# PCB.net
KiCad netlist of a schematic drawn in EAGLE
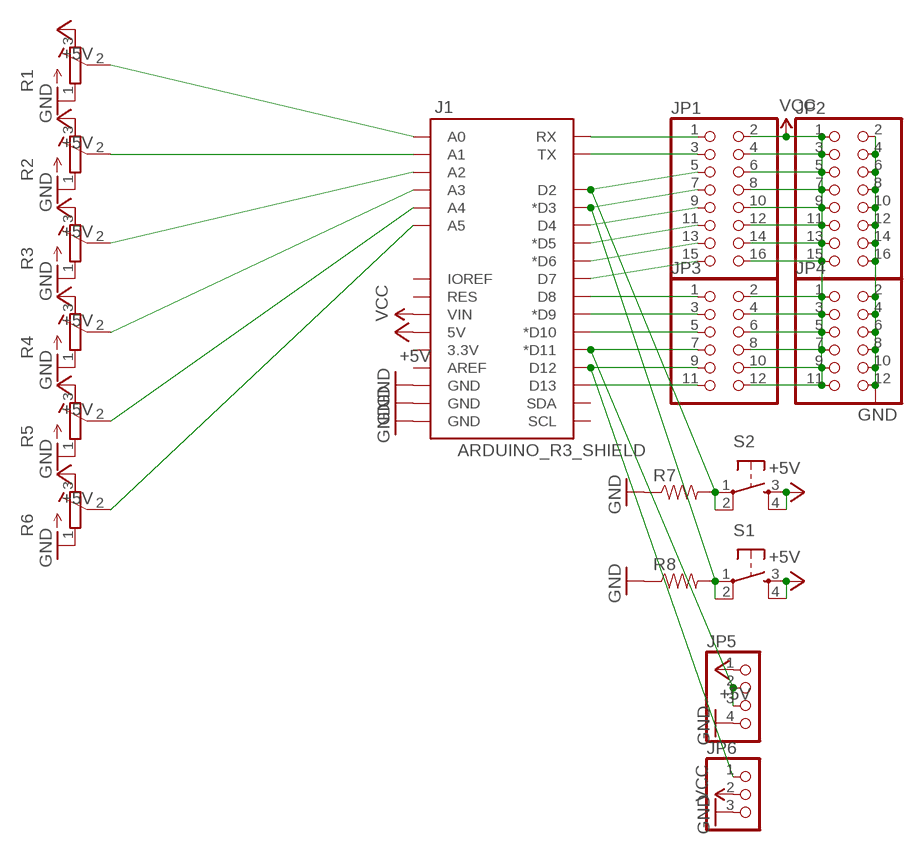
[diagram p0: schematic, sheet 1]

(export (version "E")
  (design (tool "Eeschema 10.0.6"))
  (components
    (comp (ref "J1")
      (value "ARDUINO_R3_SHIELD")
      (footprint "eagle-import:UNO_R3_SHIELD")
      (libsource (lib "eagle-import") (part "ARDUINO_R3_SHIELD"))
    )
    (comp (ref "JP1")
      (value "PINHD-2X8")
      (footprint "eagle-import:2X08")
      (libsource (lib "eagle-import") (part "PINHD-2X8"))
    )
    (comp (ref "JP2")
      (value "PINHD-2X8")
      (footprint "eagle-import:2X08")
      (libsource (lib "eagle-import") (part "PINHD-2X8"))
    )
    (comp (ref "JP3")
      (value "PINHD-2X6")
      (footprint "eagle-import:2X06")
      (libsource (lib "eagle-import") (part "PINHD-2X6"))
    )
    (comp (ref "JP4")
      (value "PINHD-2X6")
      (footprint "eagle-import:2X06")
      (libsource (lib "eagle-import") (part "PINHD-2X6"))
    )
    (comp (ref "JP5")
      (value "PINHD-1X4")
      (footprint "eagle-import:1X04")
      (libsource (lib "eagle-import") (part "PINHD-1X4"))
    )
    (comp (ref "JP6")
      (value "PINHD-1X3")
      (footprint "eagle-import:1X03")
      (libsource (lib "eagle-import") (part "PINHD-1X3"))
    )
    (comp (ref "R1")
      (value "R-TRIMM3339P")
      (footprint "eagle-import:RTRIM3339P")
      (libsource (lib "eagle-import") (part "R-TRIMM3339P"))
    )
    (comp (ref "R2")
      (value "R-TRIMM3339P")
      (footprint "eagle-import:RTRIM3339P")
      (libsource (lib "eagle-import") (part "R-TRIMM3339P"))
    )
    (comp (ref "R3")
      (value "R-TRIMM3339P")
      (footprint "eagle-import:RTRIM3339P")
      (libsource (lib "eagle-import") (part "R-TRIMM3339P"))
    )
    (comp (ref "R4")
      (value "R-TRIMM3339P")
      (footprint "eagle-import:RTRIM3339P")
      (libsource (lib "eagle-import") (part "R-TRIMM3339P"))
    )
    (comp (ref "R5")
      (value "R-TRIMM3339P")
      (footprint "eagle-import:RTRIM3339P")
      (libsource (lib "eagle-import") (part "R-TRIMM3339P"))
    )
    (comp (ref "R6")
      (value "R-TRIMM3339P")
      (footprint "eagle-import:RTRIM3339P")
      (libsource (lib "eagle-import") (part "R-TRIMM3339P"))
    )
    (comp (ref "R7")
      (value "RESISTOREZ")
      (footprint "eagle-import:AXIAL-0.3EZ")
      (libsource (lib "eagle-import") (part "RESISTOREZ"))
    )
    (comp (ref "R8")
      (value "RESISTOREZ")
      (footprint "eagle-import:AXIAL-0.3EZ")
      (libsource (lib "eagle-import") (part "RESISTOREZ"))
    )
    (comp (ref "S1")
      (value "TAC_SWITCHPTH")
      (footprint "eagle-import:TACTILE-PTH")
      (libsource (lib "eagle-import") (part "TAC_SWITCHPTH"))
    )
    (comp (ref "S2")
      (value "TAC_SWITCHPTH")
      (footprint "eagle-import:TACTILE-PTH")
      (libsource (lib "eagle-import") (part "TAC_SWITCHPTH"))
    )
  )
  (nets
    (net (code "1") (name "+5V") (class "Default")
      (node (ref "J1") (pin "5V") (pinfunction "5V_5V") (pintype "bidirectional"))
      (node (ref "JP5") (pin "1") (pinfunction "1_1") (pintype "passive"))
      (node (ref "R1") (pin "3") (pinfunction "E_3") (pintype "passive"))
      (node (ref "R2") (pin "3") (pinfunction "E_3") (pintype "passive"))
      (node (ref "R3") (pin "3") (pinfunction "E_3") (pintype "passive"))
      (node (ref "R4") (pin "3") (pinfunction "E_3") (pintype "passive"))
      (node (ref "R5") (pin "3") (pinfunction "E_3") (pintype "passive"))
      (node (ref "R6") (pin "3") (pinfunction "E_3") (pintype "passive"))
      (node (ref "S1") (pin "3") (pinfunction "3_3") (pintype "passive"))
      (node (ref "S1") (pin "4") (pinfunction "4_4") (pintype "passive"))
      (node (ref "S2") (pin "3") (pinfunction "3_3") (pintype "passive"))
      (node (ref "S2") (pin "4") (pinfunction "4_4") (pintype "passive"))
    )
    (net (code "2") (name "GND") (class "Default")
      (node (ref "J1") (pin "GND@0") (pinfunction "GND_GND@0") (pintype "bidirectional"))
      (node (ref "J1") (pin "GND@1") (pinfunction "GND_GND@1") (pintype "bidirectional"))
      (node (ref "J1") (pin "GND@2") (pinfunction "GND_GND@2") (pintype "bidirectional"))
      (node (ref "JP2") (pin "10") (pinfunction "10_10") (pintype "passive"))
      (node (ref "JP2") (pin "12") (pinfunction "12_12") (pintype "passive"))
      (node (ref "JP2") (pin "14") (pinfunction "14_14") (pintype "passive"))
      (node (ref "JP2") (pin "16") (pinfunction "16_16") (pintype "passive"))
      (node (ref "JP2") (pin "2") (pinfunction "2_2") (pintype "passive"))
      (node (ref "JP2") (pin "4") (pinfunction "4_4") (pintype "passive"))
      (node (ref "JP2") (pin "6") (pinfunction "6_6") (pintype "passive"))
      (node (ref "JP2") (pin "8") (pinfunction "8_8") (pintype "passive"))
      (node (ref "JP4") (pin "10") (pinfunction "10_10") (pintype "passive"))
      (node (ref "JP4") (pin "12") (pinfunction "12_12") (pintype "passive"))
      (node (ref "JP4") (pin "2") (pinfunction "2_2") (pintype "passive"))
      (node (ref "JP4") (pin "4") (pinfunction "4_4") (pintype "passive"))
      (node (ref "JP4") (pin "6") (pinfunction "6_6") (pintype "passive"))
      (node (ref "JP4") (pin "8") (pinfunction "8_8") (pintype "passive"))
      (node (ref "JP5") (pin "4") (pinfunction "4_4") (pintype "passive"))
      (node (ref "JP6") (pin "3") (pinfunction "3_3") (pintype "passive"))
      (node (ref "R1") (pin "1") (pinfunction "A_1") (pintype "passive"))
      (node (ref "R2") (pin "1") (pinfunction "A_1") (pintype "passive"))
      (node (ref "R3") (pin "1") (pinfunction "A_1") (pintype "passive"))
      (node (ref "R4") (pin "1") (pinfunction "A_1") (pintype "passive"))
      (node (ref "R5") (pin "1") (pinfunction "A_1") (pintype "passive"))
      (node (ref "R6") (pin "1") (pinfunction "A_1") (pintype "passive"))
      (node (ref "R7") (pin "P$1") (pinfunction "1_P$1") (pintype "passive"))
      (node (ref "R8") (pin "P$1") (pinfunction "1_P$1") (pintype "passive"))
    )
    (net (code "3") (name "Net-(J1-*D3)") (class "Default")
      (node (ref "J1") (pin "D3") (pinfunction "*D3_D3") (pintype "bidirectional"))
      (node (ref "JP1") (pin "7") (pinfunction "7_7") (pintype "passive"))
      (node (ref "R8") (pin "P$2") (pinfunction "2_P$2") (pintype "passive"))
      (node (ref "S1") (pin "1") (pinfunction "1_1") (pintype "passive"))
      (node (ref "S1") (pin "2") (pinfunction "2_2") (pintype "passive"))
    )
    (net (code "4") (name "Net-(J1-*D5)") (class "Default")
      (node (ref "J1") (pin "D5") (pinfunction "*D5_D5") (pintype "bidirectional"))
      (node (ref "JP1") (pin "11") (pinfunction "11_11") (pintype "passive"))
    )
    (net (code "5") (name "Net-(J1-*D6)") (class "Default")
      (node (ref "J1") (pin "D6") (pinfunction "*D6_D6") (pintype "bidirectional"))
      (node (ref "JP1") (pin "13") (pinfunction "13_13") (pintype "passive"))
    )
    (net (code "6") (name "Net-(J1-*D9)") (class "Default")
      (node (ref "J1") (pin "D9") (pinfunction "*D9_D9") (pintype "bidirectional"))
      (node (ref "JP3") (pin "3") (pinfunction "3_3") (pintype "passive"))
    )
    (net (code "7") (name "Net-(J1-*D10)") (class "Default")
      (node (ref "J1") (pin "D10") (pinfunction "*D10_D10") (pintype "bidirectional"))
      (node (ref "JP3") (pin "5") (pinfunction "5_5") (pintype "passive"))
    )
    (net (code "8") (name "Net-(J1-*D11)") (class "Default")
      (node (ref "J1") (pin "D11") (pinfunction "*D11_D11") (pintype "bidirectional"))
      (node (ref "JP3") (pin "7") (pinfunction "7_7") (pintype "passive"))
      (node (ref "JP5") (pin "2") (pinfunction "2_2") (pintype "passive"))
      (node (ref "JP5") (pin "3") (pinfunction "3_3") (pintype "passive"))
    )
    (net (code "9") (name "Net-(J1-PadD4)") (class "Default")
      (node (ref "J1") (pin "D4") (pinfunction "D4_D4") (pintype "bidirectional"))
      (node (ref "JP1") (pin "9") (pinfunction "9_9") (pintype "passive"))
    )
    (net (code "10") (name "Net-(J1-PadD7)") (class "Default")
      (node (ref "J1") (pin "D7") (pinfunction "D7_D7") (pintype "bidirectional"))
      (node (ref "JP1") (pin "15") (pinfunction "15_15") (pintype "passive"))
    )
    (net (code "11") (name "Net-(J1-PadD8)") (class "Default")
      (node (ref "J1") (pin "D8") (pinfunction "D8_D8") (pintype "bidirectional"))
      (node (ref "JP3") (pin "1") (pinfunction "1_1") (pintype "passive"))
    )
    (net (code "12") (name "Net-(J1-PadD12)") (class "Default")
      (node (ref "J1") (pin "D12") (pinfunction "D12_D12") (pintype "bidirectional"))
      (node (ref "JP3") (pin "9") (pinfunction "9_9") (pintype "passive"))
      (node (ref "JP6") (pin "1") (pinfunction "1_1") (pintype "passive"))
    )
    (net (code "13") (name "Net-(J1-PadD13)") (class "Default")
      (node (ref "J1") (pin "D13") (pinfunction "D13_D13") (pintype "bidirectional"))
      (node (ref "JP3") (pin "11") (pinfunction "11_11") (pintype "passive"))
    )
    (net (code "14") (name "Net-(J1-PadRX)") (class "Default")
      (node (ref "J1") (pin "RX") (pinfunction "RX_RX") (pintype "bidirectional"))
      (node (ref "JP1") (pin "1") (pinfunction "1_1") (pintype "passive"))
    )
    (net (code "15") (name "Net-(J1-PadTX)") (class "Default")
      (node (ref "J1") (pin "TX") (pinfunction "TX_TX") (pintype "bidirectional"))
      (node (ref "JP1") (pin "3") (pinfunction "3_3") (pintype "passive"))
    )
    (net (code "16") (name "Net-(R1-S)") (class "Default")
      (node (ref "J1") (pin "A0") (pinfunction "A0_A0") (pintype "bidirectional"))
      (node (ref "R1") (pin "2") (pinfunction "S_2") (pintype "passive"))
    )
    (net (code "17") (name "Net-(R2-S)") (class "Default")
      (node (ref "J1") (pin "A1") (pinfunction "A1_A1") (pintype "bidirectional"))
      (node (ref "R2") (pin "2") (pinfunction "S_2") (pintype "passive"))
    )
    (net (code "18") (name "Net-(R3-S)") (class "Default")
      (node (ref "J1") (pin "A2") (pinfunction "A2_A2") (pintype "bidirectional"))
      (node (ref "R3") (pin "2") (pinfunction "S_2") (pintype "passive"))
    )
    (net (code "19") (name "Net-(R4-S)") (class "Default")
      (node (ref "J1") (pin "A3") (pinfunction "A3_A3") (pintype "bidirectional"))
      (node (ref "R4") (pin "2") (pinfunction "S_2") (pintype "passive"))
    )
    (net (code "20") (name "Net-(R5-S)") (class "Default")
      (node (ref "J1") (pin "A4") (pinfunction "A4_A4") (pintype "bidirectional"))
      (node (ref "R5") (pin "2") (pinfunction "S_2") (pintype "passive"))
    )
    (net (code "21") (name "Net-(R6-S)") (class "Default")
      (node (ref "J1") (pin "A5") (pinfunction "A5_A5") (pintype "bidirectional"))
      (node (ref "R6") (pin "2") (pinfunction "S_2") (pintype "passive"))
    )
    (net (code "22") (name "Net-(R7-2)") (class "Default")
      (node (ref "J1") (pin "D2") (pinfunction "D2_D2") (pintype "bidirectional"))
      (node (ref "JP1") (pin "5") (pinfunction "5_5") (pintype "passive"))
      (node (ref "R7") (pin "P$2") (pinfunction "2_P$2") (pintype "passive"))
      (node (ref "S2") (pin "1") (pinfunction "1_1") (pintype "passive"))
      (node (ref "S2") (pin "2") (pinfunction "2_2") (pintype "passive"))
    )
    (net (code "23") (name "VCC") (class "Default")
      (node (ref "J1") (pin "VIN") (pinfunction "VIN_VIN") (pintype "bidirectional"))
      (node (ref "JP1") (pin "10") (pinfunction "10_10") (pintype "passive"))
      (node (ref "JP1") (pin "12") (pinfunction "12_12") (pintype "passive"))
      (node (ref "JP1") (pin "14") (pinfunction "14_14") (pintype "passive"))
      (node (ref "JP1") (pin "16") (pinfunction "16_16") (pintype "passive"))
      (node (ref "JP1") (pin "2") (pinfunction "2_2") (pintype "passive"))
      (node (ref "JP1") (pin "4") (pinfunction "4_4") (pintype "passive"))
      (node (ref "JP1") (pin "6") (pinfunction "6_6") (pintype "passive"))
      (node (ref "JP1") (pin "8") (pinfunction "8_8") (pintype "passive"))
      (node (ref "JP2") (pin "1") (pinfunction "1_1") (pintype "passive"))
      (node (ref "JP2") (pin "11") (pinfunction "11_11") (pintype "passive"))
      (node (ref "JP2") (pin "13") (pinfunction "13_13") (pintype "passive"))
      (node (ref "JP2") (pin "15") (pinfunction "15_15") (pintype "passive"))
      (node (ref "JP2") (pin "3") (pinfunction "3_3") (pintype "passive"))
      (node (ref "JP2") (pin "5") (pinfunction "5_5") (pintype "passive"))
      (node (ref "JP2") (pin "7") (pinfunction "7_7") (pintype "passive"))
      (node (ref "JP2") (pin "9") (pinfunction "9_9") (pintype "passive"))
      (node (ref "JP3") (pin "10") (pinfunction "10_10") (pintype "passive"))
      (node (ref "JP3") (pin "12") (pinfunction "12_12") (pintype "passive"))
      (node (ref "JP3") (pin "2") (pinfunction "2_2") (pintype "passive"))
      (node (ref "JP3") (pin "4") (pinfunction "4_4") (pintype "passive"))
      (node (ref "JP3") (pin "6") (pinfunction "6_6") (pintype "passive"))
      (node (ref "JP3") (pin "8") (pinfunction "8_8") (pintype "passive"))
      (node (ref "JP4") (pin "1") (pinfunction "1_1") (pintype "passive"))
      (node (ref "JP4") (pin "11") (pinfunction "11_11") (pintype "passive"))
      (node (ref "JP4") (pin "3") (pinfunction "3_3") (pintype "passive"))
      (node (ref "JP4") (pin "5") (pinfunction "5_5") (pintype "passive"))
      (node (ref "JP4") (pin "7") (pinfunction "7_7") (pintype "passive"))
      (node (ref "JP4") (pin "9") (pinfunction "9_9") (pintype "passive"))
      (node (ref "JP6") (pin "2") (pinfunction "2_2") (pintype "passive"))
    )
    (net (code "24") (name "unconnected-(J1-Pad3.3V)") (class "Default")
      (node (ref "J1") (pin "3.3V") (pinfunction "3.3V_3.3V") (pintype "bidirectional"))
    )
    (net (code "25") (name "unconnected-(J1-PadAREF)") (class "Default")
      (node (ref "J1") (pin "AREF") (pinfunction "AREF_AREF") (pintype "bidirectional"))
    )
    (net (code "26") (name "unconnected-(J1-PadIOREF)") (class "Default")
      (node (ref "J1") (pin "IOREF") (pinfunction "IOREF_IOREF") (pintype "bidirectional"))
    )
    (net (code "27") (name "unconnected-(J1-PadRES)") (class "Default")
      (node (ref "J1") (pin "RES") (pinfunction "RES_RES") (pintype "bidirectional"))
    )
    (net (code "28") (name "unconnected-(J1-PadSCL)") (class "Default")
      (node (ref "J1") (pin "SCL") (pinfunction "SCL_SCL") (pintype "bidirectional"))
    )
    (net (code "29") (name "unconnected-(J1-PadSDA)") (class "Default")
      (node (ref "J1") (pin "SDA") (pinfunction "SDA_SDA") (pintype "bidirectional"))
    )
  )
)
